# USB_Headers.net
KiCad netlist of a schematic drawn in Altium Designer
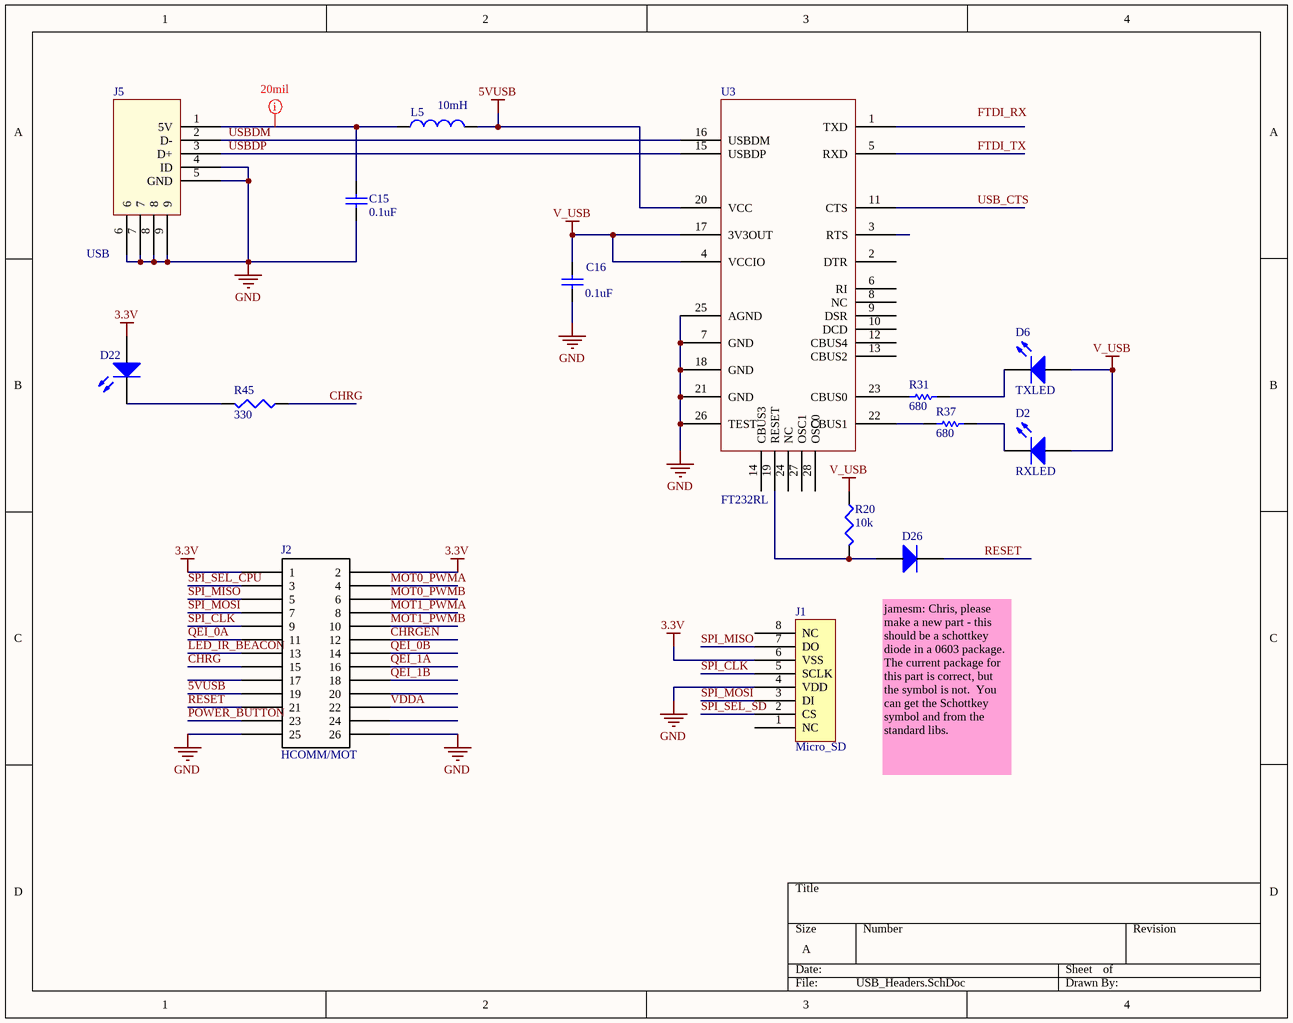
[diagram p0: USB_Headers.SchDoc]

(export (version "E")
  (design (tool "Eeschema 10.0.6"))
  (components
    (comp (ref "C15")
      (value "0.1uF")
      (footprint "CAPC1005L")
      (description "Capacitor")
      (fields (field (name "PUBLISHER") "Altium Limited"))
      (libsource (lib "Miscellaneous Devices") (part "Cap"))
    )
    (comp (ref "C16")
      (value "0.1uF")
      (footprint "CAPC1005L")
      (description "Capacitor")
      (fields (field (name "PUBLISHER") "Altium Limited"))
      (libsource (lib "Miscellaneous Devices") (part "Cap"))
    )
    (comp (ref "D2")
      (value "RXLED")
      (footprint "INDC2012L")
      (description "Typical RED, GREEN, YELLOW, AMBER GaAs LED")
      (fields (field (name "PUBLISHER") "Altium Limited"))
      (libsource (lib "Miscellaneous Devices") (part "LED2"))
    )
    (comp (ref "D6")
      (value "TXLED")
      (footprint "INDC2012L")
      (description "Typical RED, GREEN, YELLOW, AMBER GaAs LED")
      (fields (field (name "PUBLISHER") "Altium Limited"))
      (libsource (lib "Miscellaneous Devices") (part "LED2"))
    )
    (comp (ref "D22")
      (value "Charge")
      (footprint "INDC2012L")
      (description "Typical RED, GREEN, YELLOW, AMBER GaAs LED")
      (fields (field (name "PUBLISHER") "Altium Limited"))
      (libsource (lib "Miscellaneous Devices") (part "LED2"))
    )
    (comp (ref "D26")
      (value "DIODE")
      (footprint "SurfaceMount(603)")
      (libsource (lib "mrone") (part "DIODE"))
    )
    (comp (ref "J1") (value "Micro_SD") (footprint "MICRO_SD") (libsource (lib "mrone") (part "MICRO_SD")))
    (comp (ref "J2")
      (value "HCOMM/MOT")
      (footprint "HeaderSM 13x2")
      (description "Header, 2X20, 50mil, IDC")
      (libsource (lib "mrone") (part "HCOMM/HMOT"))
    )
    (comp (ref "J5")
      (value "USB")
      (footprint "USB Minib (thru-hole)")
      (libsource (lib "mrone") (part "USB-ConnTH"))
    )
    (comp (ref "L5")
      (value "10mH")
      (footprint "INDC2012L")
      (description "Inductor")
      (fields (field (name "PUBLISHER") "Altium Limited"))
      (libsource (lib "Miscellaneous Devices") (part "Inductor"))
    )
    (comp (ref "R20")
      (value "10k")
      (footprint "RESC1608L")
      (description "Resistor")
      (fields (field (name "Comment") "Res3") (field (name "PUBLISHER") "Altium Limited"))
      (libsource (lib "Miscellaneous Devices") (part "Res3"))
    )
    (comp (ref "R31")
      (value "680")
      (footprint "RESC1608L")
      (description "Resistor")
      (fields (field (name "PUBLISHER") "Altium Limited"))
      (libsource (lib "Miscellaneous Devices") (part "Res1"))
    )
    (comp (ref "R37")
      (value "680")
      (footprint "RESC1608L")
      (description "Resistor")
      (fields (field (name "PUBLISHER") "Altium Limited"))
      (libsource (lib "Miscellaneous Devices") (part "Res1"))
    )
    (comp (ref "R45")
      (value "330")
      (footprint "RESC1608L")
      (description "Resistor")
      (fields (field (name "Comment") "Res3") (field (name "PUBLISHER") "Altium Limited"))
      (libsource (lib "Miscellaneous Devices") (part "Res3"))
    )
    (comp (ref "U3") (value "FT232RL") (footprint "SSOP-28") (libsource (lib "mrone") (part "FT232RL")))
  )
  (nets
    (net (code "2") (name "/CHRG") (class "Default")
      (node (ref "J2") (pin "15") (pinfunction "15_15") (pintype "passive"))
      (node (ref "R45") (pin "1") (pinfunction "1_1") (pintype "passive"))
    )
    (net (code "3") (name "/CHRGEN") (class "Default")
      (node (ref "J2") (pin "12") (pinfunction "12_12") (pintype "passive"))
    )
    (net (code "5") (name "/FTDI_TX") (class "Default")
      (node (ref "U3") (pin "5") (pinfunction "RXD_5") (pintype "passive"))
    )
    (net (code "6") (name "/LED_IR_BEACON") (class "Default")
      (node (ref "J2") (pin "13") (pinfunction "13_13") (pintype "passive"))
    )
    (net (code "7") (name "/MOT0_PWMA") (class "Default")
      (node (ref "J2") (pin "4") (pinfunction "4_4") (pintype "passive"))
    )
    (net (code "8") (name "/MOT0_PWMB") (class "Default")
      (node (ref "J2") (pin "6") (pinfunction "6_6") (pintype "passive"))
    )
    (net (code "9") (name "/MOT1_PWMA") (class "Default")
      (node (ref "J2") (pin "8") (pinfunction "8_8") (pintype "passive"))
    )
    (net (code "10") (name "/MOT1_PWMB") (class "Default")
      (node (ref "J2") (pin "10") (pinfunction "10_10") (pintype "passive"))
    )
    (net (code "11") (name "/POWER_BUTTON") (class "Default")
      (node (ref "J2") (pin "23") (pinfunction "23_23") (pintype "passive"))
    )
    (net (code "12") (name "/QEI_0A") (class "Default")
      (node (ref "J2") (pin "11") (pinfunction "11_11") (pintype "passive"))
    )
    (net (code "13") (name "/QEI_0B") (class "Default")
      (node (ref "J2") (pin "14") (pinfunction "14_14") (pintype "passive"))
    )
    (net (code "14") (name "/QEI_1A") (class "Default")
      (node (ref "J2") (pin "16") (pinfunction "16_16") (pintype "passive"))
    )
    (net (code "15") (name "/QEI_1B") (class "Default")
      (node (ref "J2") (pin "18") (pinfunction "18_18") (pintype "passive"))
    )
    (net (code "16") (name "/RESET") (class "Default")
      (node (ref "D26") (pin "2") (pinfunction "K_2") (pintype "passive"))
      (node (ref "J2") (pin "21") (pinfunction "21_21") (pintype "passive"))
    )
    (net (code "17") (name "/SPI_CLK") (class "Default")
      (node (ref "J1") (pin "5") (pinfunction "SCLK_5") (pintype "passive"))
      (node (ref "J2") (pin "9") (pinfunction "9_9") (pintype "passive"))
    )
    (net (code "18") (name "/SPI_MISO") (class "Default")
      (node (ref "J1") (pin "7") (pinfunction "DO_7") (pintype "passive"))
      (node (ref "J2") (pin "5") (pinfunction "5_5") (pintype "passive"))
    )
    (net (code "19") (name "/SPI_MOSI") (class "Default")
      (node (ref "J1") (pin "3") (pinfunction "DI_3") (pintype "passive"))
      (node (ref "J2") (pin "7") (pinfunction "7_7") (pintype "passive"))
    )
    (net (code "20") (name "/SPI_SEL_CPU") (class "Default")
      (node (ref "J2") (pin "3") (pinfunction "3_3") (pintype "passive"))
    )
    (net (code "21") (name "/SPI_SEL_SD") (class "Default")
      (node (ref "J1") (pin "2") (pinfunction "CS_2") (pintype "passive"))
    )
    (net (code "22") (name "/USBDM") (class "Default")
      (node (ref "J5") (pin "2") (pinfunction "D-_2") (pintype "passive"))
      (node (ref "U3") (pin "16") (pinfunction "USBDM_16") (pintype "passive"))
    )
    (net (code "23") (name "/USBDP") (class "Default")
      (node (ref "J5") (pin "3") (pinfunction "D+_3") (pintype "passive"))
      (node (ref "U3") (pin "15") (pinfunction "USBDP_15") (pintype "passive"))
    )
    (net (code "24") (name "/USB_CTS") (class "Default")
      (node (ref "U3") (pin "11") (pinfunction "CTS_11") (pintype "passive"))
    )
    (net (code "25") (name "/VDDA") (class "Default")
      (node (ref "J2") (pin "22") (pinfunction "22_22") (pintype "passive"))
    )
    (net (code "26") (name "3.3V") (class "Default")
      (node (ref "D22") (pin "1") (pinfunction "A_1") (pintype "passive"))
      (node (ref "J1") (pin "6") (pinfunction "VSS_6") (pintype "passive"))
      (node (ref "J2") (pin "1") (pinfunction "1_1") (pintype "passive"))
      (node (ref "J2") (pin "2") (pinfunction "2_2") (pintype "passive"))
    )
    (net (code "27") (name "5VUSB") (class "Default")
      (node (ref "J2") (pin "19") (pinfunction "19_19") (pintype "passive"))
      (node (ref "L5") (pin "2") (pinfunction "2_2") (pintype "passive"))
      (node (ref "U3") (pin "20") (pinfunction "VCC_20") (pintype "passive"))
    )
    (net (code "28") (name "GND") (class "Default")
      (node (ref "C15") (pin "1") (pinfunction "1_1") (pintype "passive"))
      (node (ref "C16") (pin "1") (pinfunction "1_1") (pintype "passive"))
      (node (ref "J1") (pin "4") (pinfunction "VDD_4") (pintype "passive"))
      (node (ref "J2") (pin "25") (pinfunction "25_25") (pintype "passive"))
      (node (ref "J2") (pin "26") (pinfunction "26_26") (pintype "passive"))
      (node (ref "J5") (pin "4") (pinfunction "ID_4") (pintype "passive"))
      (node (ref "J5") (pin "5") (pinfunction "GND_5") (pintype "passive"))
      (node (ref "J5") (pin "6") (pinfunction "6_6") (pintype "passive"))
      (node (ref "J5") (pin "7") (pinfunction "7_7") (pintype "passive"))
      (node (ref "J5") (pin "8") (pinfunction "8_8") (pintype "passive"))
      (node (ref "J5") (pin "9") (pinfunction "9_9") (pintype "passive"))
      (node (ref "U3") (pin "18") (pinfunction "GND_18") (pintype "passive"))
      (node (ref "U3") (pin "21") (pinfunction "GND_21") (pintype "passive"))
      (node (ref "U3") (pin "25") (pinfunction "AGND_25") (pintype "passive"))
      (node (ref "U3") (pin "26") (pinfunction "TEST_26") (pintype "passive"))
      (node (ref "U3") (pin "7") (pinfunction "GND_7") (pintype "passive"))
    )
    (net (code "29") (name "Net-(D2-K)") (class "Default")
      (node (ref "D2") (pin "2") (pinfunction "K_2") (pintype "passive"))
      (node (ref "R37") (pin "2") (pinfunction "2_2") (pintype "passive"))
    )
    (net (code "30") (name "Net-(D6-K)") (class "Default")
      (node (ref "D6") (pin "2") (pinfunction "K_2") (pintype "passive"))
      (node (ref "R31") (pin "2") (pinfunction "2_2") (pintype "passive"))
    )
    (net (code "31") (name "Net-(D22-K)") (class "Default")
      (node (ref "D22") (pin "2") (pinfunction "K_2") (pintype "passive"))
      (node (ref "R45") (pin "2") (pinfunction "2_2") (pintype "passive"))
    )
    (net (code "32") (name "Net-(D26-A)") (class "Default")
      (node (ref "D26") (pin "1") (pinfunction "A_1") (pintype "passive"))
      (node (ref "R20") (pin "2") (pinfunction "2_2") (pintype "passive"))
      (node (ref "U3") (pin "19") (pinfunction "RESET_19") (pintype "passive"))
    )
    (net (code "33") (name "Net-(J5-5V)") (class "Default")
      (node (ref "C15") (pin "2") (pinfunction "2_2") (pintype "passive"))
      (node (ref "J5") (pin "1") (pinfunction "5V_1") (pintype "passive"))
      (node (ref "L5") (pin "1") (pinfunction "1_1") (pintype "passive"))
    )
    (net (code "34") (name "Net-(U3-CBUS0)") (class "Default")
      (node (ref "R31") (pin "1") (pinfunction "1_1") (pintype "passive"))
      (node (ref "U3") (pin "23") (pinfunction "CBUS0_23") (pintype "passive"))
    )
    (net (code "35") (name "Net-(U3-CBUS1)") (class "Default")
      (node (ref "R37") (pin "1") (pinfunction "1_1") (pintype "passive"))
      (node (ref "U3") (pin "22") (pinfunction "CBUS1_22") (pintype "passive"))
    )
    (net (code "36") (name "V_USB") (class "Default")
      (node (ref "C16") (pin "2") (pinfunction "2_2") (pintype "passive"))
      (node (ref "D2") (pin "1") (pinfunction "A_1") (pintype "passive"))
      (node (ref "D6") (pin "1") (pinfunction "A_1") (pintype "passive"))
      (node (ref "R20") (pin "1") (pinfunction "1_1") (pintype "passive"))
      (node (ref "U3") (pin "17") (pinfunction "3V3OUT_17") (pintype "passive"))
      (node (ref "U3") (pin "4") (pinfunction "VCCIO_4") (pintype "passive"))
    )
    (net (code "37") (name "unconnected-(J1-NC-Pad1)") (class "Default")
      (node (ref "J1") (pin "1") (pinfunction "NC_1") (pintype "passive"))
    )
    (net (code "38") (name "unconnected-(J1-NC-Pad8)") (class "Default")
      (node (ref "J1") (pin "8") (pinfunction "NC_8") (pintype "passive"))
    )
    (net (code "39") (name "unconnected-(J2-Pad17)") (class "Default")
      (node (ref "J2") (pin "17") (pinfunction "17_17") (pintype "passive"))
    )
    (net (code "40") (name "unconnected-(J2-Pad20)") (class "Default")
      (node (ref "J2") (pin "20") (pinfunction "20_20") (pintype "passive"))
    )
    (net (code "41") (name "unconnected-(J2-Pad24)") (class "Default")
      (node (ref "J2") (pin "24") (pinfunction "24_24") (pintype "passive"))
    )
    (net (code "42") (name "unconnected-(U3-CBUS2-Pad13)") (class "Default")
      (node (ref "U3") (pin "13") (pinfunction "CBUS2_13") (pintype "passive"))
    )
    (net (code "43") (name "unconnected-(U3-CBUS3-Pad14)") (class "Default")
      (node (ref "U3") (pin "14") (pinfunction "CBUS3_14") (pintype "passive"))
    )
    (net (code "44") (name "unconnected-(U3-CBUS4-Pad12)") (class "Default")
      (node (ref "U3") (pin "12") (pinfunction "CBUS4_12") (pintype "passive"))
    )
    (net (code "45") (name "unconnected-(U3-DCD-Pad10)") (class "Default")
      (node (ref "U3") (pin "10") (pinfunction "DCD_10") (pintype "passive"))
    )
    (net (code "46") (name "unconnected-(U3-DSR-Pad9)") (class "Default")
      (node (ref "U3") (pin "9") (pinfunction "DSR_9") (pintype "passive"))
    )
    (net (code "47") (name "unconnected-(U3-DTR-Pad2)") (class "Default")
      (node (ref "U3") (pin "2") (pinfunction "DTR_2") (pintype "passive"))
    )
    (net (code "48") (name "unconnected-(U3-NC-Pad8)") (class "Default")
      (node (ref "U3") (pin "8") (pinfunction "NC_8") (pintype "passive"))
    )
    (net (code "49") (name "unconnected-(U3-NC-Pad24)") (class "Default")
      (node (ref "U3") (pin "24") (pinfunction "NC_24") (pintype "passive"))
    )
    (net (code "50") (name "unconnected-(U3-OSC0-Pad28)") (class "Default")
      (node (ref "U3") (pin "28") (pinfunction "OSC0_28") (pintype "passive"))
    )
    (net (code "51") (name "unconnected-(U3-OSC1-Pad27)") (class "Default")
      (node (ref "U3") (pin "27") (pinfunction "OSC1_27") (pintype "passive"))
    )
    (net (code "52") (name "unconnected-(U3-RI-Pad6)") (class "Default")
      (node (ref "U3") (pin "6") (pinfunction "RI_6") (pintype "passive"))
    )
    (net (code "53") (name "unconnected-(U3-RTS-Pad3)") (class "Default")
      (node (ref "U3") (pin "3") (pinfunction "RTS_3") (pintype "passive"))
    )
    (net (code "54") (name "unconnected-(U3-TXD-Pad1)") (class "Default")
      (node (ref "U3") (pin "1") (pinfunction "TXD_1") (pintype "passive"))
    )
  )
)
